# PIN_bias_voltage.net
KiCad netlist of a schematic drawn in Altium Designer
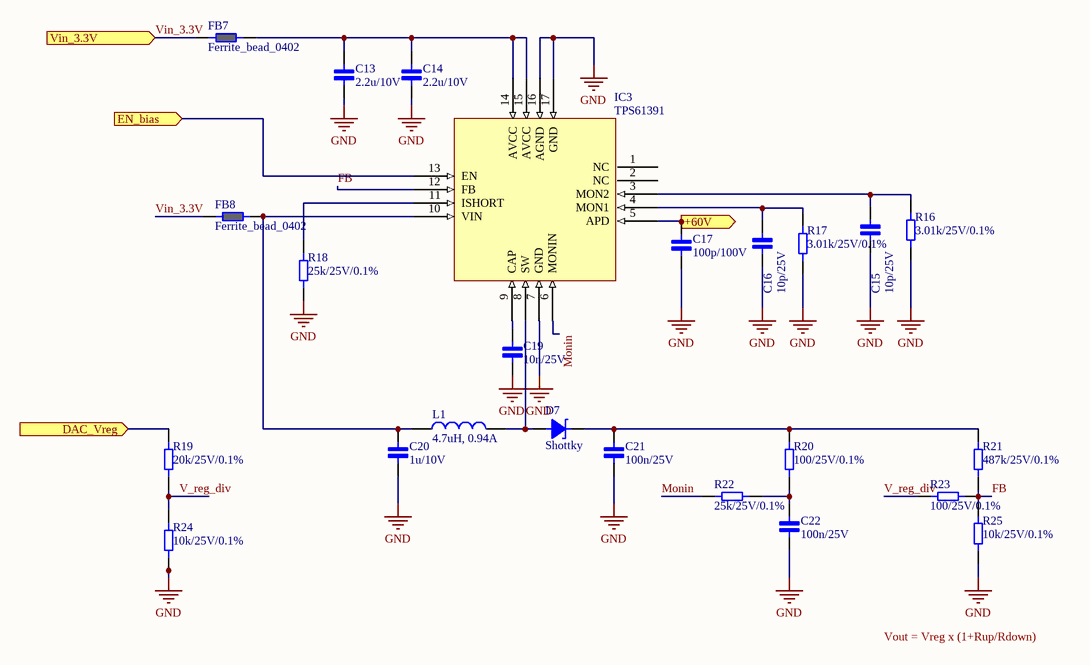
[diagram p0: PIN_bias_voltage.SchDoc]

(export (version "E")
  (design (tool "Eeschema 10.0.6"))
  (components
    (comp (ref "C13")
      (value "2.2u/10V")
      (footprint "Cap_0402")
      (description "Ceramic Capacitor 2.2uF / 0402 / 10V / ±5%, Wurth Elektronik MLCC")
      (libsource (lib "Cubesat_lib") (part "Cap_0402_2.2u"))
    )
    (comp (ref "C14")
      (value "2.2u/10V")
      (footprint "Cap_0402")
      (description "Ceramic Capacitor 2.2uF / 0402 / 10V / ±5%, Wurth Elektronik MLCC")
      (libsource (lib "Cubesat_lib") (part "Cap_0402_2.2u"))
    )
    (comp (ref "C15")
      (value "10p/25V")
      (footprint "Cap_0402")
      (description "0402 / 25V / ±5%, Wurth Elektronik MLCC")
      (libsource (lib "Cubesat_lib") (part "Cap_0402_10p"))
    )
    (comp (ref "C16")
      (value "10p/25V")
      (footprint "Cap_0402")
      (description "0402 / 25V / ±5%, Wurth Elektronik MLCC")
      (libsource (lib "Cubesat_lib") (part "Cap_0402_10p"))
    )
    (comp (ref "C17")
      (value "100p/100V")
      (footprint "Cap_0402")
      (description "0402 / 100V / ±5%, Wurth Elektronik MLCC")
      (libsource (lib "Cubesat_lib") (part "Cap_0402_100p_hv"))
    )
    (comp (ref "C19")
      (value "10n/25V")
      (footprint "Cap_0402")
      (description "Ceramic Capacitor 10n / 0402 / 25V / ±5%, Wurth Elektronik MLCC")
      (libsource (lib "Cubesat_lib") (part "Cap_0402_10n"))
    )
    (comp (ref "C20")
      (value "1u/10V")
      (footprint "Cap_0402")
      (description "Ceramic Capacitor 1uF / 0402 / 10V / ±5%, Wurth Elektronik MLCC")
      (libsource (lib "Cubesat_lib") (part "Cap_0402_1u"))
    )
    (comp (ref "C21")
      (value "100n/25V")
      (footprint "Cap_0402")
      (description "Ceramic Capacitor 100n / 0402 / 25V / ±5%, Wurth Elektronik MLCC")
      (libsource (lib "Cubesat_lib") (part "Cap_0402_100n"))
    )
    (comp (ref "C22")
      (value "100n/25V")
      (footprint "Cap_0402")
      (description "Ceramic Capacitor 100n / 0402 / 25V / ±5%, Wurth Elektronik MLCC")
      (libsource (lib "Cubesat_lib") (part "Cap_0402_100n"))
    )
    (comp (ref "D7")
      (value "Shottky")
      (footprint "SOD323")
      (description "Schottky diode, 90V, 100mA, 1.2V, 4ns")
      (libsource (lib "Cubesat_lib") (part "1SS355VMFHTE-17"))
    )
    (comp (ref "FB7")
      (value "Ferrite_bead_0402")
      (footprint "FERRITE_0402")
      (description "Ferrite bead, wurth 74269241102")
      (libsource (lib "Cubesat_lib") (part "Ferrite_bead_0402"))
    )
    (comp (ref "FB8")
      (value "Ferrite_bead_0402")
      (footprint "FERRITE_0402")
      (description "Ferrite bead, wurth 74269241102")
      (libsource (lib "Cubesat_lib") (part "Ferrite_bead_0402"))
    )
    (comp (ref "IC3")
      (value "TPS61391")
      (footprint "WQFN16")
      (description "TPS61391 85-VOUT Boost Converter with Current Mirror Integrated")
      (libsource (lib "Cubesat_lib") (part "TPS61391"))
    )
    (comp (ref "L1")
      (value "4.7uH, 0.94A")
      (footprint "WE-MAPI_2510")
      (description "WE-MAPI SMT Power Inductor, size 2510, 4.7uH, 0.94A")
      (fields
        (field (name "MANUFACTURER") "Wurth Elektronik")
        (field (name "MANUFACTURER PART NUMBER") "74438323047")
      )
      (libsource (lib "WE-MAPI_tiny_inductors") (part "74438323047"))
    )
    (comp (ref "R16")
      (value "3.01k/25V/0.1%")
      (footprint "RES_0402")
      (description "Vishay, thin film resistor 3.01k/25V/0.1%")
      (libsource (lib "Cubesat_lib") (part "Res_0402_3.01k"))
    )
    (comp (ref "R17")
      (value "3.01k/25V/0.1%")
      (footprint "RES_0402")
      (description "Vishay, thin film resistor 3.01k/25V/0.1%")
      (libsource (lib "Cubesat_lib") (part "Res_0402_3.01k"))
    )
    (comp (ref "R18")
      (value "25k/25V/0.1%")
      (footprint "RES_0402")
      (description "Vishay, thin film resistor 25k/25V/0.1%")
      (libsource (lib "Cubesat_lib") (part "Res_0402_25k"))
    )
    (comp (ref "R19")
      (value "20k/25V/0.1%")
      (footprint "RES_0402")
      (description "Vishay, thin film resistor 20k/25V/0.1%")
      (libsource (lib "Cubesat_lib") (part "Res_0402_20k"))
    )
    (comp (ref "R20")
      (value "100/25V/0.1%")
      (footprint "RES_0402")
      (description "Vishay, thin film resistor 100/25V/0.1%")
      (libsource (lib "Cubesat_lib") (part "Res_0402_100"))
    )
    (comp (ref "R21")
      (value "487k/25V/0.1%")
      (footprint "RES_0402")
      (description "Vishay, thin film resistor 487k/25V/0.1%")
      (libsource (lib "Cubesat_lib") (part "Res_0402_487k"))
    )
    (comp (ref "R22")
      (value "25k/25V/0.1%")
      (footprint "RES_0402")
      (description "Vishay, thin film resistor 25k/25V/0.1%")
      (libsource (lib "") (part "Res_0402_25k_1"))
    )
    (comp (ref "R23")
      (value "100/25V/0.1%")
      (footprint "RES_0402")
      (description "Vishay, thin film resistor 100/25V/0.1%")
      (libsource (lib "") (part "Res_0402_100_1"))
    )
    (comp (ref "R24")
      (value "10k/25V/0.1%")
      (footprint "RES_0402")
      (description "Vishay, thin film resistor 10k/25V/0.1%")
      (libsource (lib "Cubesat_lib") (part "Res_0402_10k"))
    )
    (comp (ref "R25")
      (value "10k/25V/0.1%")
      (footprint "RES_0402")
      (description "Vishay, thin film resistor 10k/25V/0.1%")
      (libsource (lib "Cubesat_lib") (part "Res_0402_10k"))
    )
  )
  (nets
    (net (code "1") (name "/+60V") (class "Default")
      (node (ref "C17") (pin "2") (pinfunction "2_2") (pintype "passive"))
      (node (ref "IC3") (pin "5") (pinfunction "APD_5") (pintype "input"))
    )
    (net (code "2") (name "/DAC_Vreg") (class "Default")
      (node (ref "R19") (pin "2") (pinfunction "2_2") (pintype "passive"))
    )
    (net (code "3") (name "/EN_bias") (class "Default")
      (node (ref "IC3") (pin "13") (pinfunction "EN_13") (pintype "input"))
    )
    (net (code "4") (name "/FB") (class "Default")
      (node (ref "IC3") (pin "12") (pinfunction "FB_12") (pintype "input"))
      (node (ref "R21") (pin "1") (pinfunction "1_1") (pintype "passive"))
      (node (ref "R23") (pin "2") (pinfunction "2_2") (pintype "passive"))
      (node (ref "R25") (pin "2") (pinfunction "2_2") (pintype "passive"))
    )
    (net (code "5") (name "/Monin") (class "Default")
      (node (ref "IC3") (pin "6") (pinfunction "MONIN_6") (pintype "input"))
      (node (ref "R22") (pin "1") (pinfunction "1_1") (pintype "passive"))
    )
    (net (code "6") (name "/V_reg_div") (class "Default")
      (node (ref "R19") (pin "1") (pinfunction "1_1") (pintype "passive"))
      (node (ref "R23") (pin "1") (pinfunction "1_1") (pintype "passive"))
      (node (ref "R24") (pin "2") (pinfunction "2_2") (pintype "passive"))
    )
    (net (code "7") (name "/Vin_3.3V") (class "Default")
      (node (ref "FB7") (pin "1") (pinfunction "1_1") (pintype "passive"))
      (node (ref "FB8") (pin "1") (pinfunction "1_1") (pintype "passive"))
    )
    (net (code "8") (name "GND") (class "Default")
      (node (ref "C13") (pin "1") (pinfunction "1_1") (pintype "passive"))
      (node (ref "C14") (pin "1") (pinfunction "1_1") (pintype "passive"))
      (node (ref "C15") (pin "1") (pinfunction "1_1") (pintype "passive"))
      (node (ref "C16") (pin "1") (pinfunction "1_1") (pintype "passive"))
      (node (ref "C17") (pin "1") (pinfunction "1_1") (pintype "passive"))
      (node (ref "C19") (pin "1") (pinfunction "1_1") (pintype "passive"))
      (node (ref "C20") (pin "1") (pinfunction "1_1") (pintype "passive"))
      (node (ref "C21") (pin "1") (pinfunction "1_1") (pintype "passive"))
      (node (ref "C22") (pin "1") (pinfunction "1_1") (pintype "passive"))
      (node (ref "IC3") (pin "16") (pinfunction "AGND_16") (pintype "input"))
      (node (ref "IC3") (pin "17") (pinfunction "GND_17") (pintype "input"))
      (node (ref "IC3") (pin "7") (pinfunction "GND_7") (pintype "input"))
      (node (ref "R16") (pin "1") (pinfunction "1_1") (pintype "passive"))
      (node (ref "R17") (pin "1") (pinfunction "1_1") (pintype "passive"))
      (node (ref "R18") (pin "1") (pinfunction "1_1") (pintype "passive"))
      (node (ref "R24") (pin "1") (pinfunction "1_1") (pintype "passive"))
      (node (ref "R25") (pin "1") (pinfunction "1_1") (pintype "passive"))
    )
    (net (code "9") (name "Net-(C13-Pad2)") (class "Default")
      (node (ref "C13") (pin "2") (pinfunction "2_2") (pintype "passive"))
      (node (ref "C14") (pin "2") (pinfunction "2_2") (pintype "passive"))
      (node (ref "FB7") (pin "2") (pinfunction "2_2") (pintype "passive"))
      (node (ref "IC3") (pin "14") (pinfunction "AVCC_14") (pintype "input"))
      (node (ref "IC3") (pin "15") (pinfunction "AVCC_15") (pintype "input"))
    )
    (net (code "10") (name "Net-(C21-Pad2)") (class "Default")
      (node (ref "C21") (pin "2") (pinfunction "2_2") (pintype "passive"))
      (node (ref "D7") (pin "2") (pinfunction "2_2") (pintype "passive"))
      (node (ref "R20") (pin "2") (pinfunction "2_2") (pintype "passive"))
      (node (ref "R21") (pin "2") (pinfunction "2_2") (pintype "passive"))
    )
    (net (code "11") (name "Net-(C22-Pad2)") (class "Default")
      (node (ref "C22") (pin "2") (pinfunction "2_2") (pintype "passive"))
      (node (ref "R20") (pin "1") (pinfunction "1_1") (pintype "passive"))
      (node (ref "R22") (pin "2") (pinfunction "2_2") (pintype "passive"))
    )
    (net (code "12") (name "Net-(IC3-CAP)") (class "Default")
      (node (ref "C19") (pin "2") (pinfunction "2_2") (pintype "passive"))
      (node (ref "IC3") (pin "9") (pinfunction "CAP_9") (pintype "input"))
    )
    (net (code "13") (name "Net-(IC3-ISHORT)") (class "Default")
      (node (ref "IC3") (pin "11") (pinfunction "ISHORT_11") (pintype "input"))
      (node (ref "R18") (pin "2") (pinfunction "2_2") (pintype "passive"))
    )
    (net (code "14") (name "Net-(IC3-MON1)") (class "Default")
      (node (ref "C16") (pin "2") (pinfunction "2_2") (pintype "passive"))
      (node (ref "IC3") (pin "4") (pinfunction "MON1_4") (pintype "input"))
      (node (ref "R17") (pin "2") (pinfunction "2_2") (pintype "passive"))
    )
    (net (code "15") (name "Net-(IC3-MON2)") (class "Default")
      (node (ref "C15") (pin "2") (pinfunction "2_2") (pintype "passive"))
      (node (ref "IC3") (pin "3") (pinfunction "MON2_3") (pintype "input"))
      (node (ref "R16") (pin "2") (pinfunction "2_2") (pintype "passive"))
    )
    (net (code "16") (name "Net-(IC3-SW)") (class "Default")
      (node (ref "D7") (pin "1") (pinfunction "1_1") (pintype "passive"))
      (node (ref "IC3") (pin "8") (pinfunction "SW_8") (pintype "input"))
      (node (ref "L1") (pin "2") (pinfunction "2_2") (pintype "passive"))
    )
    (net (code "17") (name "Net-(IC3-VIN)") (class "Default")
      (node (ref "C20") (pin "2") (pinfunction "2_2") (pintype "passive"))
      (node (ref "FB8") (pin "2") (pinfunction "2_2") (pintype "passive"))
      (node (ref "IC3") (pin "10") (pinfunction "VIN_10") (pintype "input"))
      (node (ref "L1") (pin "1") (pinfunction "1_1") (pintype "passive"))
    )
    (net (code "18") (name "unconnected-(IC3-NC-Pad1)") (class "Default")
      (node (ref "IC3") (pin "1") (pinfunction "NC_1") (pintype "passive"))
    )
    (net (code "19") (name "unconnected-(IC3-NC-Pad2)") (class "Default")
      (node (ref "IC3") (pin "2") (pinfunction "NC_2") (pintype "passive"))
    )
  )
)
